# untitled.net
KiCad netlist of a schematic drawn in EAGLE
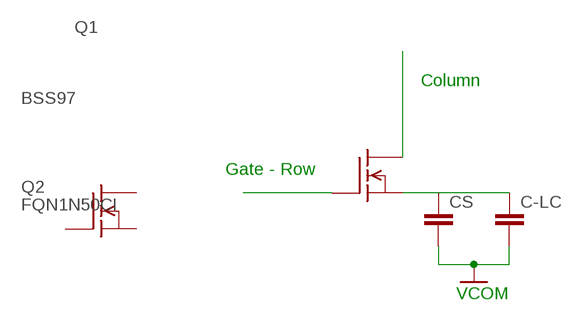
[diagram p0: schematic, sheet 1]

(export (version "E")
  (design (tool "Eeschema 10.0.6"))
  (components
    (comp (ref "C-LC")
      (value "CAP0402-CAP")
      (footprint "eagle-import:0402-CAP")
      (libsource (lib "eagle-import") (part "CAP0402-CAP"))
    )
    (comp (ref "CS")
      (value "CAP0402-CAP")
      (footprint "eagle-import:0402-CAP")
      (libsource (lib "eagle-import") (part "CAP0402-CAP"))
    )
    (comp (ref "Q1")
      (value "BSS97")
      (footprint "eagle-import:TO202")
      (libsource (lib "eagle-import") (part "BSS97"))
    )
    (comp (ref "Q2")
      (value "FQN1N50CI")
      (footprint "eagle-import:TO92-INLINE")
      (libsource (lib "eagle-import") (part "FQN1N50CI"))
    )
  )
  (nets
    (net (code "1") (name "GND") (class "Default")
      (node (ref "C-LC") (pin "2") (pinfunction "2_2") (pintype "passive"))
      (node (ref "CS") (pin "2") (pinfunction "2_2") (pintype "passive"))
    )
    (net (code "2") (name "Net-(Q1-S)") (class "Default")
      (node (ref "C-LC") (pin "1") (pinfunction "1_1") (pintype "passive"))
      (node (ref "CS") (pin "1") (pinfunction "1_1") (pintype "passive"))
      (node (ref "Q1") (pin "1") (pinfunction "S_1") (pintype "passive"))
    )
    (net (code "3") (name "unconnected-(Q1-D-Pad2)") (class "Default")
      (node (ref "Q1") (pin "2") (pinfunction "D_2") (pintype "passive"))
    )
    (net (code "4") (name "unconnected-(Q1-G-Pad3)") (class "Default")
      (node (ref "Q1") (pin "3") (pinfunction "G_3") (pintype "passive"))
    )
    (net (code "5") (name "unconnected-(Q2-D-Pad1)") (class "Default")
      (node (ref "Q2") (pin "1") (pinfunction "D_1") (pintype "passive"))
    )
    (net (code "6") (name "unconnected-(Q2-G-Pad2)") (class "Default")
      (node (ref "Q2") (pin "2") (pinfunction "G_2") (pintype "passive"))
    )
    (net (code "7") (name "unconnected-(Q2-S-Pad3)") (class "Default")
      (node (ref "Q2") (pin "3") (pinfunction "S_3") (pintype "passive"))
    )
  )
)
